# thermistorADC.net
KiCad netlist of a schematic drawn in Altium Designer
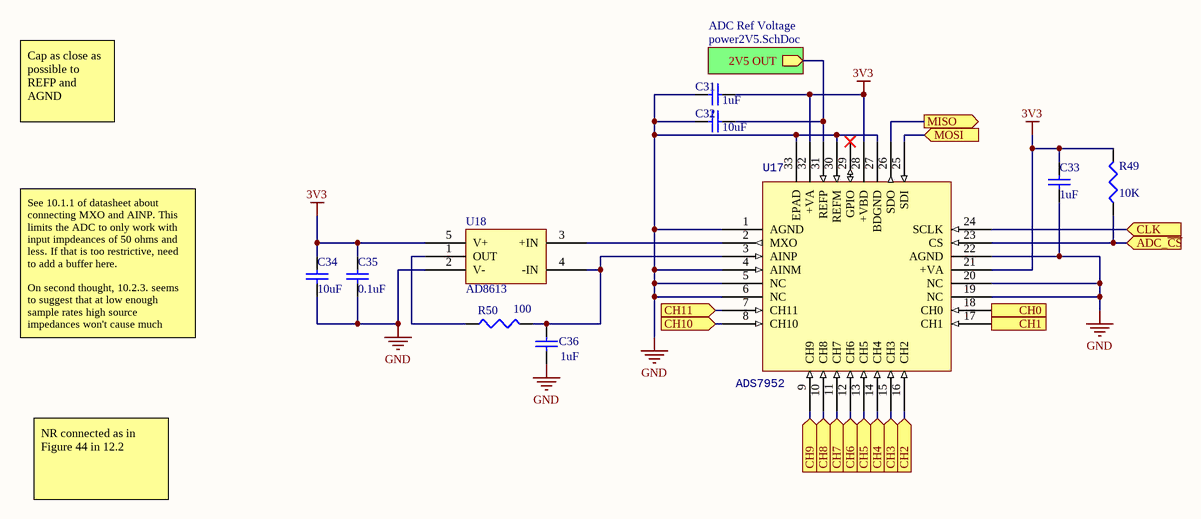
[diagram p0: thermistorADC.SchDoc]

(export (version "E")
  (design (tool "Eeschema 10.0.6"))
  (components
    (comp (ref "C31")
      (value "1uF")
      (footprint "1608[0603]")
      (description "Capacitor (Semiconductor SIM Model)")
      (fields (field (name "PUBLISHER") "Altium Limited"))
      (libsource (lib "Miscellaneous Devices") (part "Cap Semi"))
    )
    (comp (ref "C32")
      (value "10uF")
      (footprint "1608[0603]")
      (description "Capacitor")
      (fields (field (name "PUBLISHER") "Altium Limited"))
      (libsource (lib "Miscellaneous Devices") (part "Cap"))
    )
    (comp (ref "C33")
      (value "1uF")
      (footprint "1608[0603]")
      (description "Capacitor (Semiconductor SIM Model)")
      (fields (field (name "PUBLISHER") "Altium Limited"))
      (libsource (lib "Miscellaneous Devices") (part "Cap Semi"))
    )
    (comp (ref "C34")
      (value "10uF")
      (footprint "1608[0603]")
      (description "Capacitor (Semiconductor SIM Model)")
      (fields (field (name "PUBLISHER") "Altium Limited"))
      (libsource (lib "Miscellaneous Devices") (part "Cap Semi"))
    )
    (comp (ref "C35")
      (value "0.1uF")
      (footprint "1608[0603]")
      (description "Capacitor (Semiconductor SIM Model)")
      (fields (field (name "PUBLISHER") "Altium Limited"))
      (libsource (lib "Miscellaneous Devices") (part "Cap Semi"))
    )
    (comp (ref "C36")
      (value "1uF")
      (footprint "1608[0603]")
      (description "Capacitor (Semiconductor SIM Model)")
      (fields (field (name "PUBLISHER") "Altium Limited"))
      (libsource (lib "Miscellaneous Devices") (part "Cap Semi"))
    )
    (comp (ref "R49")
      (value "10K")
      (footprint "J1-0603")
      (description "Resistor")
      (fields (field (name "PUBLISHER") "Altium Limited"))
      (libsource (lib "Miscellaneous Devices") (part "Res3"))
    )
    (comp (ref "R50")
      (value "100")
      (footprint "J1-0603")
      (description "Resistor")
      (fields (field (name "PUBLISHER") "Altium Limited"))
      (libsource (lib "Miscellaneous Devices") (part "Res3"))
    )
    (comp (ref "U17") (value "ADS7952") (description "ADC") (libsource (lib "EPS") (part "ADS7952")))
    (comp (ref "U18")
      (value "AD8613")
      (footprint "SOP-65P200X125-5N")
      (description "Low power, low noise rail-to-rail op-amp.")
      (libsource (lib "PAY") (part "AD8613"))
    )
  )
  (nets
    (net (code "1") (name "/2V5 OUT") (class "Default")
      (node (ref "C32") (pin "2") (pinfunction "2_2") (pintype "passive"))
      (node (ref "U17") (pin "31") (pinfunction "REFP_31") (pintype "input"))
    )
    (net (code "2") (name "/ADC_~{CS}") (class "Default")
      (node (ref "R49") (pin "1") (pinfunction "1_1") (pintype "passive"))
      (node (ref "U17") (pin "23") (pinfunction "CS_23") (pintype "input"))
    )
    (net (code "3") (name "/CH0") (class "Default")
      (node (ref "U17") (pin "18") (pinfunction "CH0_18") (pintype "input"))
    )
    (net (code "4") (name "/CH1") (class "Default")
      (node (ref "U17") (pin "17") (pinfunction "CH1_17") (pintype "input"))
    )
    (net (code "5") (name "/CH2") (class "Default")
      (node (ref "U17") (pin "16") (pinfunction "CH2_16") (pintype "input"))
    )
    (net (code "6") (name "/CH3") (class "Default")
      (node (ref "U17") (pin "15") (pinfunction "CH3_15") (pintype "input"))
    )
    (net (code "7") (name "/CH4") (class "Default")
      (node (ref "U17") (pin "14") (pinfunction "CH4_14") (pintype "input"))
    )
    (net (code "8") (name "/CH5") (class "Default")
      (node (ref "U17") (pin "13") (pinfunction "CH5_13") (pintype "input"))
    )
    (net (code "9") (name "/CH6") (class "Default")
      (node (ref "U17") (pin "12") (pinfunction "CH6_12") (pintype "input"))
    )
    (net (code "10") (name "/CH7") (class "Default")
      (node (ref "U17") (pin "11") (pinfunction "CH7_11") (pintype "input"))
    )
    (net (code "11") (name "/CH8") (class "Default")
      (node (ref "U17") (pin "10") (pinfunction "CH8_10") (pintype "input"))
    )
    (net (code "12") (name "/CH9") (class "Default")
      (node (ref "U17") (pin "9") (pinfunction "CH9_9") (pintype "input"))
    )
    (net (code "13") (name "/CH10") (class "Default")
      (node (ref "U17") (pin "8") (pinfunction "CH10_8") (pintype "input"))
    )
    (net (code "14") (name "/CH11") (class "Default")
      (node (ref "U17") (pin "7") (pinfunction "CH11_7") (pintype "input"))
    )
    (net (code "15") (name "/CLK") (class "Default")
      (node (ref "U17") (pin "24") (pinfunction "SCLK_24") (pintype "input"))
    )
    (net (code "16") (name "/MISO") (class "Default")
      (node (ref "U17") (pin "26") (pinfunction "SDO_26") (pintype "output"))
    )
    (net (code "17") (name "/MOSI") (class "Default")
      (node (ref "U17") (pin "25") (pinfunction "SDI_25") (pintype "input"))
    )
    (net (code "18") (name "3V3") (class "Default")
      (node (ref "C31") (pin "2") (pinfunction "2_2") (pintype "passive"))
      (node (ref "C33") (pin "2") (pinfunction "2_2") (pintype "passive"))
      (node (ref "C34") (pin "2") (pinfunction "2_2") (pintype "passive"))
      (node (ref "C35") (pin "2") (pinfunction "2_2") (pintype "passive"))
      (node (ref "R49") (pin "2") (pinfunction "2_2") (pintype "passive"))
      (node (ref "U17") (pin "21") (pinfunction "+VA_21") (pintype "power_in"))
      (node (ref "U17") (pin "28") (pinfunction "+VBD_28") (pintype "power_in"))
      (node (ref "U17") (pin "32") (pinfunction "+VA_32") (pintype "power_in"))
      (node (ref "U18") (pin "5") (pinfunction "V+_5") (pintype "passive"))
    )
    (net (code "19") (name "GND") (class "Default")
      (node (ref "C31") (pin "1") (pinfunction "1_1") (pintype "passive"))
      (node (ref "C32") (pin "1") (pinfunction "1_1") (pintype "passive"))
      (node (ref "C33") (pin "1") (pinfunction "1_1") (pintype "passive"))
      (node (ref "C34") (pin "1") (pinfunction "1_1") (pintype "passive"))
      (node (ref "C35") (pin "1") (pinfunction "1_1") (pintype "passive"))
      (node (ref "C36") (pin "1") (pinfunction "1_1") (pintype "passive"))
      (node (ref "U17") (pin "1") (pinfunction "AGND_1") (pintype "power_in"))
      (node (ref "U17") (pin "19") (pinfunction "NC_19") (pintype "passive"))
      (node (ref "U17") (pin "20") (pinfunction "NC_20") (pintype "passive"))
      (node (ref "U17") (pin "22") (pinfunction "AGND_22") (pintype "power_in"))
      (node (ref "U17") (pin "27") (pinfunction "BDGND_27") (pintype "power_in"))
      (node (ref "U17") (pin "30") (pinfunction "REFM_30") (pintype "input"))
      (node (ref "U17") (pin "33") (pinfunction "EPAD_33") (pintype "passive"))
      (node (ref "U17") (pin "4") (pinfunction "AINM_4") (pintype "input"))
      (node (ref "U17") (pin "5") (pinfunction "NC_5") (pintype "passive"))
      (node (ref "U17") (pin "6") (pinfunction "NC_6") (pintype "passive"))
      (node (ref "U18") (pin "2") (pinfunction "V-_2") (pintype "passive"))
    )
    (net (code "20") (name "Net-(U17-AINP)") (class "Default")
      (node (ref "C36") (pin "2") (pinfunction "2_2") (pintype "passive"))
      (node (ref "R50") (pin "2") (pinfunction "2_2") (pintype "passive"))
      (node (ref "U17") (pin "3") (pinfunction "AINP_3") (pintype "input"))
      (node (ref "U18") (pin "4") (pinfunction "-IN_4") (pintype "passive"))
    )
    (net (code "21") (name "Net-(U17-MXO)") (class "Default")
      (node (ref "U17") (pin "2") (pinfunction "MXO_2") (pintype "output"))
      (node (ref "U18") (pin "3") (pinfunction "+IN_3") (pintype "passive"))
    )
    (net (code "22") (name "Net-(U18-OUT)") (class "Default")
      (node (ref "R50") (pin "1") (pinfunction "1_1") (pintype "passive"))
      (node (ref "U18") (pin "1") (pinfunction "OUT_1") (pintype "passive"))
    )
    (net (code "23") (name "unconnected-(U17-GPIO-Pad29)") (class "Default")
      (node (ref "U17") (pin "29") (pinfunction "GPIO_29") (pintype "bidirectional+no_connect"))
    )
  )
)
